# design.net
KiCad netlist of a schematic drawn in EasyEDA Pro
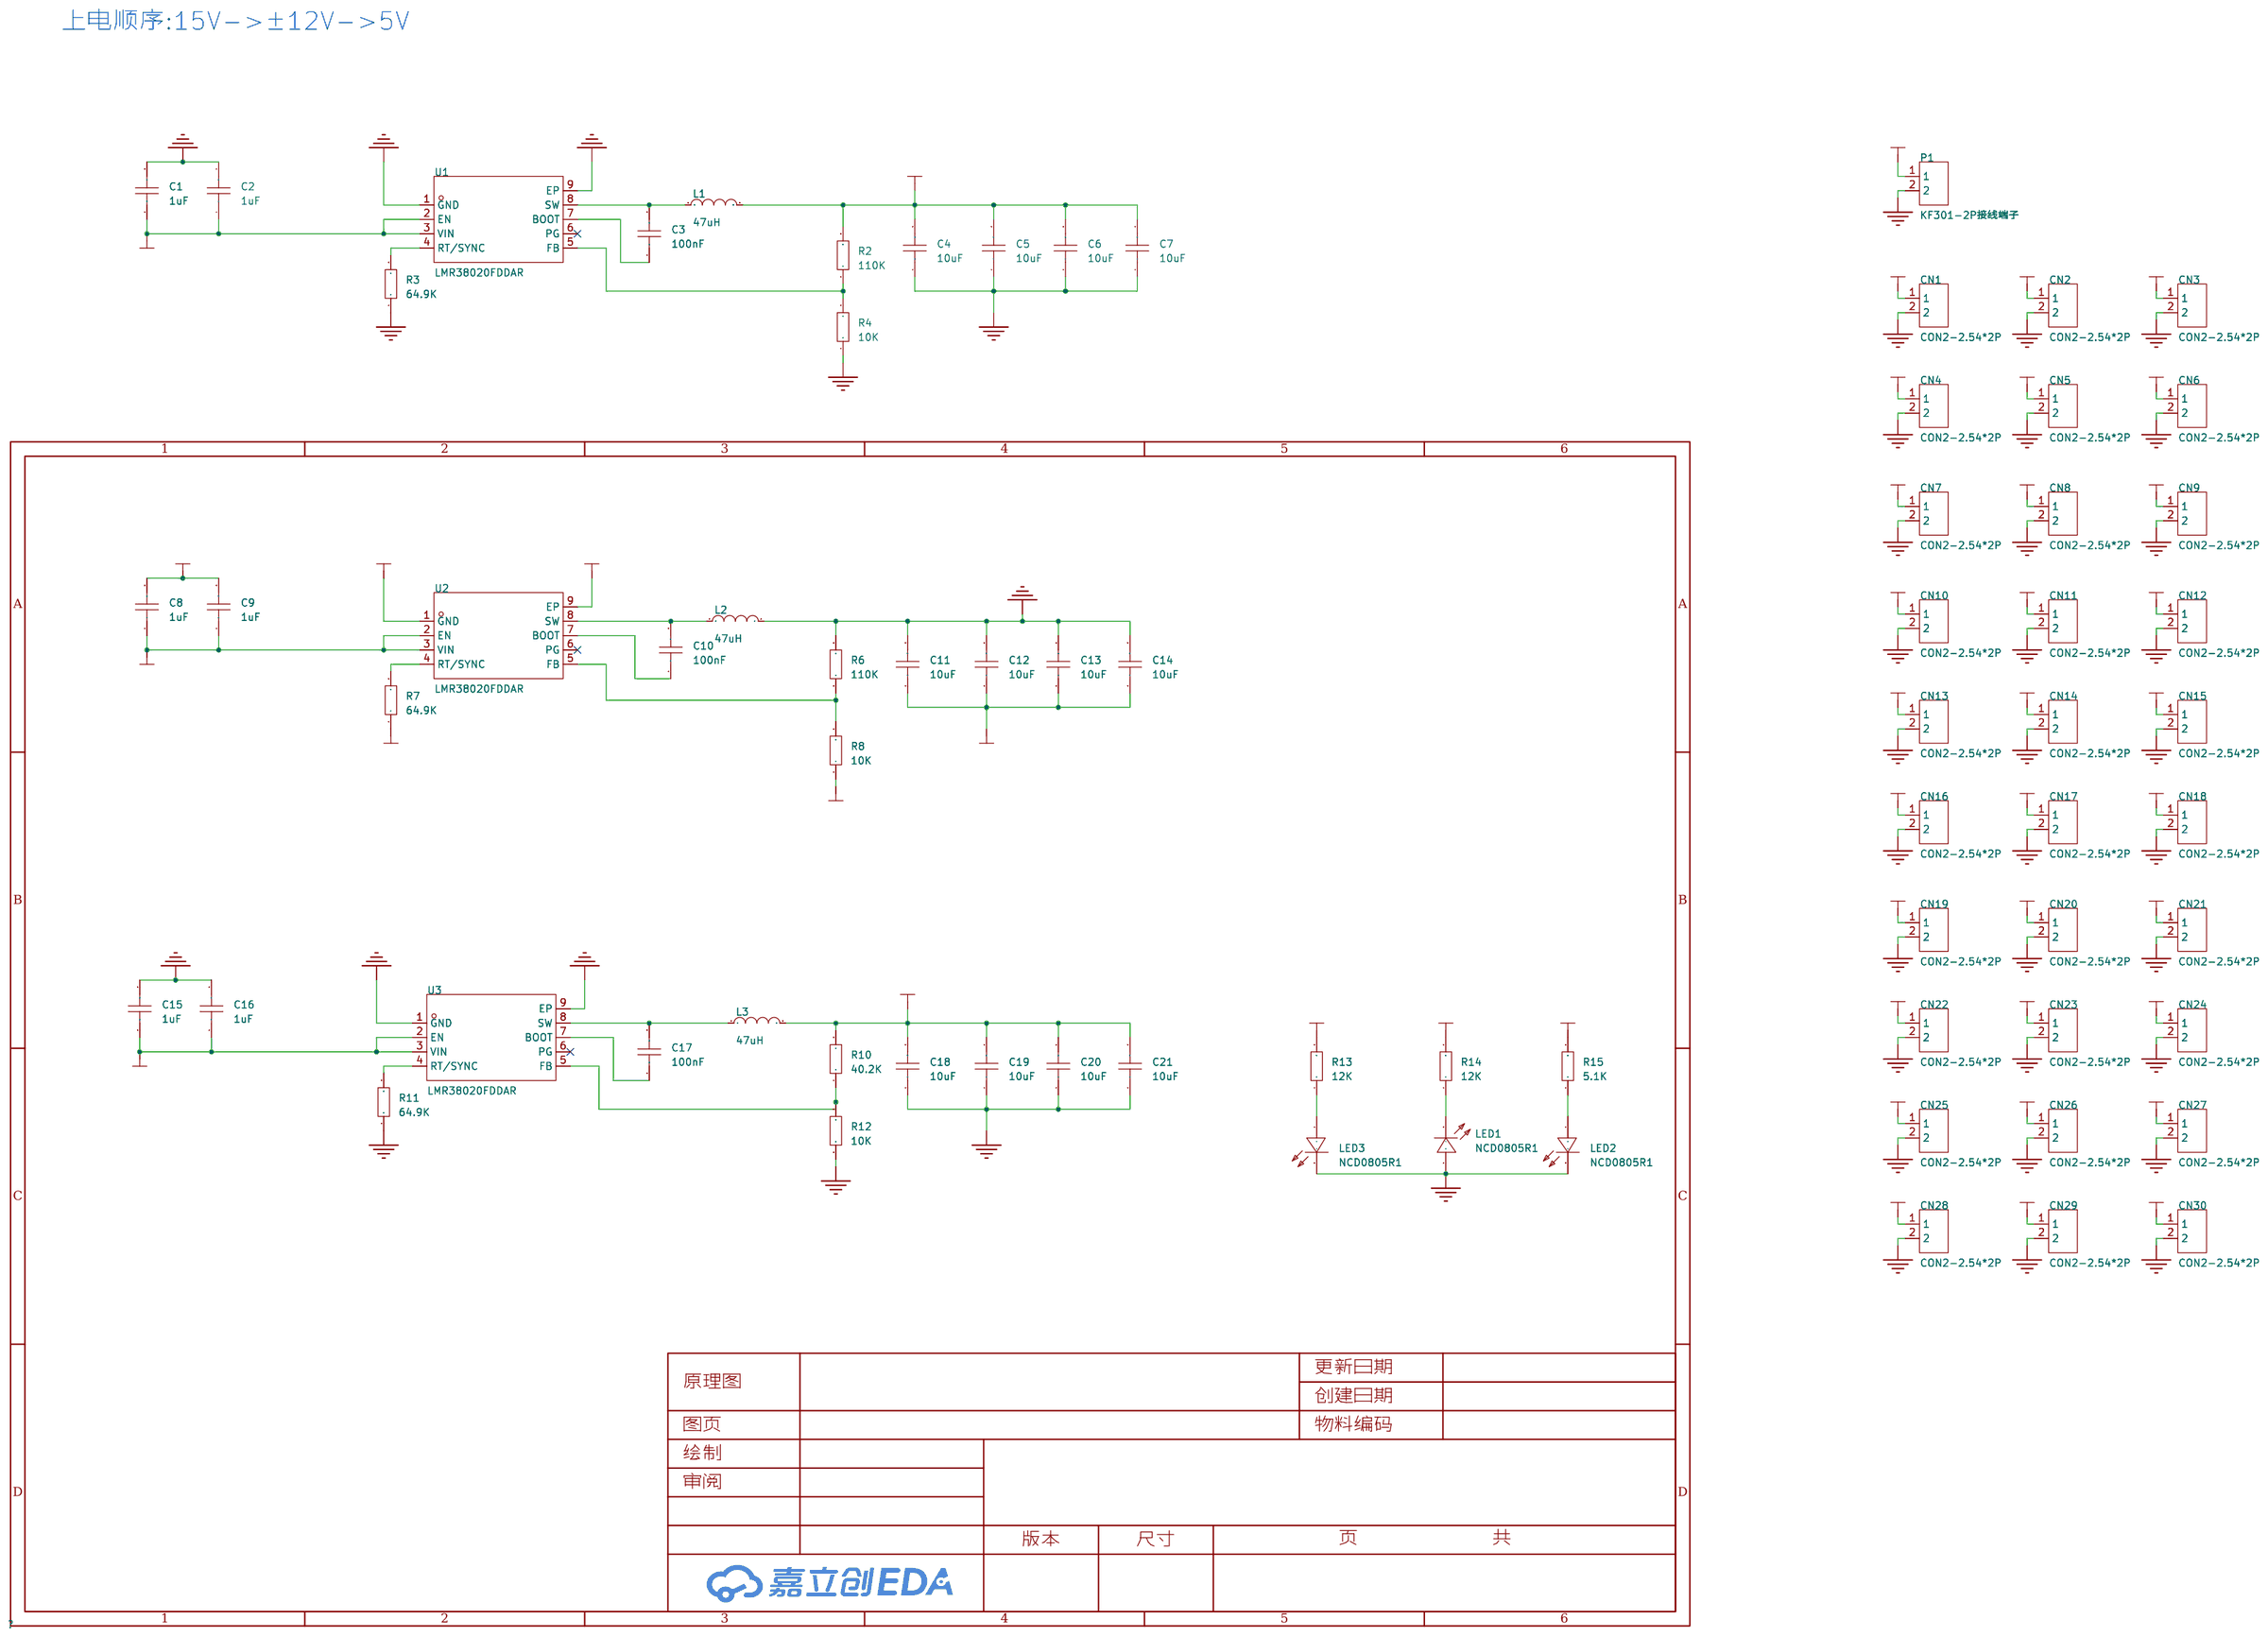
[diagram p0: schematic sheet]

(export (version "E")
  (design (tool "Eeschema 10.0.6"))
  (components
    (comp (ref "C1")
      (value "1uF")
      (footprint "easyedapro:C1206")
      (description "容值:1uF;精度:±10%;额定电压:100V;温度系数:X7R;")
      (fields (field (name "Manufacturer Part") "1206B105K101NT") (field (name "Manufacturer") "FH(风华)"))
      (libsource (lib "easyedapro") (part "1206B105K101NT"))
    )
    (comp (ref "C2")
      (value "1uF")
      (footprint "easyedapro:C1206")
      (description "容值:1uF;精度:±10%;额定电压:100V;温度系数:X7R;")
      (fields (field (name "Manufacturer Part") "1206B105K101NT") (field (name "Manufacturer") "FH(风华)"))
      (libsource (lib "easyedapro") (part "1206B105K101NT"))
    )
    (comp (ref "C3")
      (value "100nF")
      (footprint "easyedapro:C0805")
      (libsource (lib "easyedapro") (part "Capacitance"))
    )
    (comp (ref "C4")
      (value "10uF")
      (footprint "easyedapro:C1206")
      (description "容值:10uF;精度:±10%;额定电压:50V;材质(温度系数):X7R;")
      (fields
        (field (name "Manufacturer Part") "CL31B106KBHNNNE")
        (field (name "Manufacturer") "SAMSUNG(三星)")
      )
      (libsource (lib "easyedapro") (part "CL31B106KBHNNNE"))
    )
    (comp (ref "C5")
      (value "10uF")
      (footprint "easyedapro:C1206")
      (description "容值:10uF;精度:±10%;额定电压:50V;材质(温度系数):X7R;")
      (fields
        (field (name "Manufacturer Part") "CL31B106KBHNNNE")
        (field (name "Manufacturer") "SAMSUNG(三星)")
      )
      (libsource (lib "easyedapro") (part "CL31B106KBHNNNE"))
    )
    (comp (ref "C6")
      (value "10uF")
      (footprint "easyedapro:C1206")
      (description "容值:10uF;精度:±10%;额定电压:50V;材质(温度系数):X7R;")
      (fields
        (field (name "Manufacturer Part") "CL31B106KBHNNNE")
        (field (name "Manufacturer") "SAMSUNG(三星)")
      )
      (libsource (lib "easyedapro") (part "CL31B106KBHNNNE"))
    )
    (comp (ref "C7")
      (value "10uF")
      (footprint "easyedapro:C1206")
      (description "容值:10uF;精度:±10%;额定电压:50V;材质(温度系数):X7R;")
      (fields
        (field (name "Manufacturer Part") "CL31B106KBHNNNE")
        (field (name "Manufacturer") "SAMSUNG(三星)")
      )
      (libsource (lib "easyedapro") (part "CL31B106KBHNNNE"))
    )
    (comp (ref "C8")
      (value "1uF")
      (footprint "easyedapro:C1206")
      (description "容值:1uF;精度:±10%;额定电压:100V;温度系数:X7R;")
      (fields (field (name "Manufacturer Part") "1206B105K101NT") (field (name "Manufacturer") "FH(风华)"))
      (libsource (lib "easyedapro") (part "1206B105K101NT"))
    )
    (comp (ref "C9")
      (value "1uF")
      (footprint "easyedapro:C1206")
      (description "容值:1uF;精度:±10%;额定电压:100V;温度系数:X7R;")
      (fields (field (name "Manufacturer Part") "1206B105K101NT") (field (name "Manufacturer") "FH(风华)"))
      (libsource (lib "easyedapro") (part "1206B105K101NT"))
    )
    (comp (ref "C10")
      (value "100nF")
      (footprint "easyedapro:C0805")
      (libsource (lib "easyedapro") (part "Capacitance"))
    )
    (comp (ref "C11")
      (value "10uF")
      (footprint "easyedapro:C1206")
      (description "容值:10uF;精度:±10%;额定电压:50V;材质(温度系数):X7R;")
      (fields
        (field (name "Manufacturer Part") "CL31B106KBHNNNE")
        (field (name "Manufacturer") "SAMSUNG(三星)")
      )
      (libsource (lib "easyedapro") (part "CL31B106KBHNNNE"))
    )
    (comp (ref "C12")
      (value "10uF")
      (footprint "easyedapro:C1206")
      (description "容值:10uF;精度:±10%;额定电压:50V;材质(温度系数):X7R;")
      (fields
        (field (name "Manufacturer Part") "CL31B106KBHNNNE")
        (field (name "Manufacturer") "SAMSUNG(三星)")
      )
      (libsource (lib "easyedapro") (part "CL31B106KBHNNNE"))
    )
    (comp (ref "C13")
      (value "10uF")
      (footprint "easyedapro:C1206")
      (description "容值:10uF;精度:±10%;额定电压:50V;材质(温度系数):X7R;")
      (fields
        (field (name "Manufacturer Part") "CL31B106KBHNNNE")
        (field (name "Manufacturer") "SAMSUNG(三星)")
      )
      (libsource (lib "easyedapro") (part "CL31B106KBHNNNE"))
    )
    (comp (ref "C14")
      (value "10uF")
      (footprint "easyedapro:C1206")
      (description "容值:10uF;精度:±10%;额定电压:50V;材质(温度系数):X7R;")
      (fields
        (field (name "Manufacturer Part") "CL31B106KBHNNNE")
        (field (name "Manufacturer") "SAMSUNG(三星)")
      )
      (libsource (lib "easyedapro") (part "CL31B106KBHNNNE"))
    )
    (comp (ref "C15")
      (value "1uF")
      (footprint "easyedapro:C1206")
      (description "容值:1uF;精度:±10%;额定电压:100V;温度系数:X7R;")
      (fields (field (name "Manufacturer Part") "1206B105K101NT") (field (name "Manufacturer") "FH(风华)"))
      (libsource (lib "easyedapro") (part "1206B105K101NT"))
    )
    (comp (ref "C16")
      (value "1uF")
      (footprint "easyedapro:C1206")
      (description "容值:1uF;精度:±10%;额定电压:100V;温度系数:X7R;")
      (fields (field (name "Manufacturer Part") "1206B105K101NT") (field (name "Manufacturer") "FH(风华)"))
      (libsource (lib "easyedapro") (part "1206B105K101NT"))
    )
    (comp (ref "C17")
      (value "100nF")
      (footprint "easyedapro:C0805")
      (libsource (lib "easyedapro") (part "Capacitance"))
    )
    (comp (ref "C18")
      (value "10uF")
      (footprint "easyedapro:C1206")
      (description "容值:10uF;精度:±10%;额定电压:50V;材质(温度系数):X7R;")
      (fields
        (field (name "Manufacturer Part") "CL31B106KBHNNNE")
        (field (name "Manufacturer") "SAMSUNG(三星)")
      )
      (libsource (lib "easyedapro") (part "CL31B106KBHNNNE"))
    )
    (comp (ref "C19")
      (value "10uF")
      (footprint "easyedapro:C1206")
      (description "容值:10uF;精度:±10%;额定电压:50V;材质(温度系数):X7R;")
      (fields
        (field (name "Manufacturer Part") "CL31B106KBHNNNE")
        (field (name "Manufacturer") "SAMSUNG(三星)")
      )
      (libsource (lib "easyedapro") (part "CL31B106KBHNNNE"))
    )
    (comp (ref "C20")
      (value "10uF")
      (footprint "easyedapro:C1206")
      (description "容值:10uF;精度:±10%;额定电压:50V;材质(温度系数):X7R;")
      (fields
        (field (name "Manufacturer Part") "CL31B106KBHNNNE")
        (field (name "Manufacturer") "SAMSUNG(三星)")
      )
      (libsource (lib "easyedapro") (part "CL31B106KBHNNNE"))
    )
    (comp (ref "C21")
      (value "10uF")
      (footprint "easyedapro:C1206")
      (description "容值:10uF;精度:±10%;额定电压:50V;材质(温度系数):X7R;")
      (fields
        (field (name "Manufacturer Part") "CL31B106KBHNNNE")
        (field (name "Manufacturer") "SAMSUNG(三星)")
      )
      (libsource (lib "easyedapro") (part "CL31B106KBHNNNE"))
    )
    (comp (ref "CN1")
      (value "CON2-2.54*2P")
      (footprint "easyedapro:CONN-TH_2P-P2.54-V")
      (libsource (lib "easyedapro") (part "CON2-2.54*2P"))
    )
    (comp (ref "CN2")
      (value "CON2-2.54*2P")
      (footprint "easyedapro:CONN-TH_2P-P2.54-V")
      (libsource (lib "easyedapro") (part "CON2-2.54*2P"))
    )
    (comp (ref "CN3")
      (value "CON2-2.54*2P")
      (footprint "easyedapro:CONN-TH_2P-P2.54-V")
      (libsource (lib "easyedapro") (part "CON2-2.54*2P"))
    )
    (comp (ref "CN4")
      (value "CON2-2.54*2P")
      (footprint "easyedapro:CONN-TH_2P-P2.54-V")
      (libsource (lib "easyedapro") (part "CON2-2.54*2P"))
    )
    (comp (ref "CN5")
      (value "CON2-2.54*2P")
      (footprint "easyedapro:CONN-TH_2P-P2.54-V")
      (libsource (lib "easyedapro") (part "CON2-2.54*2P"))
    )
    (comp (ref "CN6")
      (value "CON2-2.54*2P")
      (footprint "easyedapro:CONN-TH_2P-P2.54-V")
      (libsource (lib "easyedapro") (part "CON2-2.54*2P"))
    )
    (comp (ref "CN7")
      (value "CON2-2.54*2P")
      (footprint "easyedapro:CONN-TH_2P-P2.54-V")
      (libsource (lib "easyedapro") (part "CON2-2.54*2P"))
    )
    (comp (ref "CN8")
      (value "CON2-2.54*2P")
      (footprint "easyedapro:CONN-TH_2P-P2.54-V")
      (libsource (lib "easyedapro") (part "CON2-2.54*2P"))
    )
    (comp (ref "CN9")
      (value "CON2-2.54*2P")
      (footprint "easyedapro:CONN-TH_2P-P2.54-V")
      (libsource (lib "easyedapro") (part "CON2-2.54*2P"))
    )
    (comp (ref "CN10")
      (value "CON2-2.54*2P")
      (footprint "easyedapro:CONN-TH_2P-P2.54-V")
      (libsource (lib "easyedapro") (part "CON2-2.54*2P"))
    )
    (comp (ref "CN11")
      (value "CON2-2.54*2P")
      (footprint "easyedapro:CONN-TH_2P-P2.54-V")
      (libsource (lib "easyedapro") (part "CON2-2.54*2P"))
    )
    (comp (ref "CN12")
      (value "CON2-2.54*2P")
      (footprint "easyedapro:CONN-TH_2P-P2.54-V")
      (libsource (lib "easyedapro") (part "CON2-2.54*2P"))
    )
    (comp (ref "CN13")
      (value "CON2-2.54*2P")
      (footprint "easyedapro:CONN-TH_2P-P2.54-V")
      (libsource (lib "easyedapro") (part "CON2-2.54*2P"))
    )
    (comp (ref "CN14")
      (value "CON2-2.54*2P")
      (footprint "easyedapro:CONN-TH_2P-P2.54-V")
      (libsource (lib "easyedapro") (part "CON2-2.54*2P"))
    )
    (comp (ref "CN15")
      (value "CON2-2.54*2P")
      (footprint "easyedapro:CONN-TH_2P-P2.54-V")
      (libsource (lib "easyedapro") (part "CON2-2.54*2P"))
    )
    (comp (ref "CN16")
      (value "CON2-2.54*2P")
      (footprint "easyedapro:CONN-TH_2P-P2.54-V")
      (libsource (lib "easyedapro") (part "CON2-2.54*2P"))
    )
    (comp (ref "CN17")
      (value "CON2-2.54*2P")
      (footprint "easyedapro:CONN-TH_2P-P2.54-V")
      (libsource (lib "easyedapro") (part "CON2-2.54*2P"))
    )
    (comp (ref "CN18")
      (value "CON2-2.54*2P")
      (footprint "easyedapro:CONN-TH_2P-P2.54-V")
      (libsource (lib "easyedapro") (part "CON2-2.54*2P"))
    )
    (comp (ref "CN19")
      (value "CON2-2.54*2P")
      (footprint "easyedapro:CONN-TH_2P-P2.54-V")
      (libsource (lib "easyedapro") (part "CON2-2.54*2P"))
    )
    (comp (ref "CN20")
      (value "CON2-2.54*2P")
      (footprint "easyedapro:CONN-TH_2P-P2.54-V")
      (libsource (lib "easyedapro") (part "CON2-2.54*2P"))
    )
    (comp (ref "CN21")
      (value "CON2-2.54*2P")
      (footprint "easyedapro:CONN-TH_2P-P2.54-V")
      (libsource (lib "easyedapro") (part "CON2-2.54*2P"))
    )
    (comp (ref "CN22")
      (value "CON2-2.54*2P")
      (footprint "easyedapro:CONN-TH_2P-P2.54-V")
      (libsource (lib "easyedapro") (part "CON2-2.54*2P"))
    )
    (comp (ref "CN23")
      (value "CON2-2.54*2P")
      (footprint "easyedapro:CONN-TH_2P-P2.54-V")
      (libsource (lib "easyedapro") (part "CON2-2.54*2P"))
    )
    (comp (ref "CN24")
      (value "CON2-2.54*2P")
      (footprint "easyedapro:CONN-TH_2P-P2.54-V")
      (libsource (lib "easyedapro") (part "CON2-2.54*2P"))
    )
    (comp (ref "CN25")
      (value "CON2-2.54*2P")
      (footprint "easyedapro:CONN-TH_2P-P2.54-V")
      (libsource (lib "easyedapro") (part "CON2-2.54*2P"))
    )
    (comp (ref "CN26")
      (value "CON2-2.54*2P")
      (footprint "easyedapro:CONN-TH_2P-P2.54-V")
      (libsource (lib "easyedapro") (part "CON2-2.54*2P"))
    )
    (comp (ref "CN27")
      (value "CON2-2.54*2P")
      (footprint "easyedapro:CONN-TH_2P-P2.54-V")
      (libsource (lib "easyedapro") (part "CON2-2.54*2P"))
    )
    (comp (ref "CN28")
      (value "CON2-2.54*2P")
      (footprint "easyedapro:CONN-TH_2P-P2.54-V")
      (libsource (lib "easyedapro") (part "CON2-2.54*2P"))
    )
    (comp (ref "CN29")
      (value "CON2-2.54*2P")
      (footprint "easyedapro:CONN-TH_2P-P2.54-V")
      (libsource (lib "easyedapro") (part "CON2-2.54*2P"))
    )
    (comp (ref "CN30")
      (value "CON2-2.54*2P")
      (footprint "easyedapro:CONN-TH_2P-P2.54-V")
      (libsource (lib "easyedapro") (part "CON2-2.54*2P"))
    )
    (comp (ref "L1")
      (value "47uH")
      (footprint "easyedapro:IND-SMD_L11.5-W10.0_FXL1040")
      (description "电感值:47uH;精度:±20%;额定电流:3.3A;饱和电流(Isat):3.5A;类型:一体成型电感;")
      (fields (field (name "Manufacturer Part") "FXL1040-470-M") (field (name "Manufacturer") "cjiang(长江微电)"))
      (libsource (lib "easyedapro") (part "FXL1040-470-M"))
    )
    (comp (ref "L2")
      (value "47uH")
      (footprint "easyedapro:IND-SMD_L11.5-W10.0_FXL1040")
      (description "电感值:47uH;精度:±20%;额定电流:3.3A;饱和电流(Isat):3.5A;类型:一体成型电感;")
      (fields (field (name "Manufacturer Part") "FXL1040-470-M") (field (name "Manufacturer") "cjiang(长江微电)"))
      (libsource (lib "easyedapro") (part "FXL1040-470-M"))
    )
    (comp (ref "L3")
      (value "47uH")
      (footprint "easyedapro:IND-SMD_L11.5-W10.0_FXL1040")
      (description "电感值:47uH;精度:±20%;额定电流:3.3A;饱和电流(Isat):3.5A;类型:一体成型电感;")
      (fields (field (name "Manufacturer Part") "FXL1040-470-M") (field (name "Manufacturer") "cjiang(长江微电)"))
      (libsource (lib "easyedapro") (part "FXL1040-470-M"))
    )
    (comp (ref "LED1")
      (value "NCD0805R1")
      (footprint "easyedapro:LED0805-R-RD")
      (fields (field (name "Manufacturer") "国星光电"))
      (libsource (lib "easyedapro") (part "FC-2012HRK-620D"))
    )
    (comp (ref "LED2")
      (value "NCD0805R1")
      (footprint "easyedapro:LED0805-R-RD")
      (fields (field (name "Manufacturer") "国星光电"))
      (libsource (lib "easyedapro") (part "FC-2012HRK-620D"))
    )
    (comp (ref "LED3")
      (value "NCD0805R1")
      (footprint "easyedapro:LED0805-R-RD")
      (fields (field (name "Manufacturer") "国星光电"))
      (libsource (lib "easyedapro") (part "FC-2012HRK-620D"))
    )
    (comp (ref "P1")
      (value "KF301-2P接线端子")
      (footprint "easyedapro:CONN-TH_XY301V-A-5.0-2P")
      (libsource (lib "easyedapro") (part "KF301-2P接线端子"))
    )
    (comp (ref "R2") (value "110K") (footprint "easyedapro:R0805") (libsource (lib "easyedapro") (part "电阻")))
    (comp (ref "R3")
      (value "64.9K")
      (footprint "easyedapro:R0805")
      (libsource (lib "easyedapro") (part "电阻"))
    )
    (comp (ref "R4") (value "10K") (footprint "easyedapro:R0805") (libsource (lib "easyedapro") (part "电阻")))
    (comp (ref "R6") (value "110K") (footprint "easyedapro:R0805") (libsource (lib "easyedapro") (part "电阻")))
    (comp (ref "R7")
      (value "64.9K")
      (footprint "easyedapro:R0805")
      (libsource (lib "easyedapro") (part "电阻"))
    )
    (comp (ref "R8") (value "10K") (footprint "easyedapro:R0805") (libsource (lib "easyedapro") (part "电阻")))
    (comp (ref "R10")
      (value "40.2K")
      (footprint "easyedapro:R0805")
      (libsource (lib "easyedapro") (part "电阻"))
    )
    (comp (ref "R11")
      (value "64.9K")
      (footprint "easyedapro:R0805")
      (libsource (lib "easyedapro") (part "电阻"))
    )
    (comp (ref "R12") (value "10K") (footprint "easyedapro:R0805") (libsource (lib "easyedapro") (part "电阻")))
    (comp (ref "R13") (value "12K") (footprint "easyedapro:R0805") (libsource (lib "easyedapro") (part "电阻")))
    (comp (ref "R14") (value "12K") (footprint "easyedapro:R0805") (libsource (lib "easyedapro") (part "电阻")))
    (comp (ref "R15")
      (value "5.1K")
      (footprint "easyedapro:R0805")
      (libsource (lib "easyedapro") (part "电阻"))
    )
    (comp (ref "U1")
      (value "LMR38020FDDAR")
      (footprint "easyedapro:ESOP-8_L4.9-W3.9-P1.27-LS6.0-BL-EP-1")
      (description "功能类型:降压型;输出类型:-;工作电压:4.2V~80V;输出电压:-;输出电流:2A;")
      (fields (field (name "Manufacturer") "TI(德州仪器)"))
      (libsource (lib "easyedapro") (part "LMR38020FDDAR"))
    )
    (comp (ref "U2")
      (value "LMR38020FDDAR")
      (footprint "easyedapro:ESOP-8_L4.9-W3.9-P1.27-LS6.0-BL-EP-1")
      (description "功能类型:降压型;输出类型:-;工作电压:4.2V~80V;输出电压:-;输出电流:2A;")
      (fields (field (name "Manufacturer") "TI(德州仪器)"))
      (libsource (lib "easyedapro") (part "LMR38020FDDAR"))
    )
    (comp (ref "U3")
      (value "LMR38020FDDAR")
      (footprint "easyedapro:ESOP-8_L4.9-W3.9-P1.27-LS6.0-BL-EP-1")
      (description "功能类型:降压型;输出类型:-;工作电压:4.2V~80V;输出电压:-;输出电流:2A;")
      (fields (field (name "Manufacturer") "TI(德州仪器)"))
      (libsource (lib "easyedapro") (part "LMR38020FDDAR"))
    )
  )
  (nets
    (net (code "1") (name "+5V") (class "Default")
      (node (ref "C18") (pin "2") (pinfunction "2_2") (pintype "unspecified"))
      (node (ref "C19") (pin "2") (pinfunction "2_2") (pintype "unspecified"))
      (node (ref "C20") (pin "2") (pinfunction "2_2") (pintype "unspecified"))
      (node (ref "C21") (pin "2") (pinfunction "2_2") (pintype "unspecified"))
      (node (ref "CN11") (pin "1") (pinfunction "1_1") (pintype "unspecified"))
      (node (ref "CN14") (pin "1") (pinfunction "1_1") (pintype "unspecified"))
      (node (ref "CN17") (pin "1") (pinfunction "1_1") (pintype "unspecified"))
      (node (ref "CN2") (pin "1") (pinfunction "1_1") (pintype "unspecified"))
      (node (ref "CN20") (pin "1") (pinfunction "1_1") (pintype "unspecified"))
      (node (ref "CN23") (pin "1") (pinfunction "1_1") (pintype "unspecified"))
      (node (ref "CN26") (pin "1") (pinfunction "1_1") (pintype "unspecified"))
      (node (ref "CN29") (pin "1") (pinfunction "1_1") (pintype "unspecified"))
      (node (ref "CN5") (pin "1") (pinfunction "1_1") (pintype "unspecified"))
      (node (ref "CN8") (pin "1") (pinfunction "1_1") (pintype "unspecified"))
      (node (ref "L3") (pin "2") (pinfunction "2_2") (pintype "unspecified"))
      (node (ref "R10") (pin "2") (pinfunction "2_2") (pintype "input"))
      (node (ref "R15") (pin "2") (pinfunction "2_2") (pintype "input"))
    )
    (net (code "2") (name "+12V") (class "Default")
      (node (ref "C4") (pin "2") (pinfunction "2_2") (pintype "unspecified"))
      (node (ref "C5") (pin "2") (pinfunction "2_2") (pintype "unspecified"))
      (node (ref "C6") (pin "2") (pinfunction "2_2") (pintype "unspecified"))
      (node (ref "C7") (pin "2") (pinfunction "2_2") (pintype "unspecified"))
      (node (ref "C8") (pin "1") (pinfunction "1_1") (pintype "unspecified"))
      (node (ref "C9") (pin "1") (pinfunction "1_1") (pintype "unspecified"))
      (node (ref "CN1") (pin "1") (pinfunction "1_1") (pintype "unspecified"))
      (node (ref "CN10") (pin "1") (pinfunction "1_1") (pintype "unspecified"))
      (node (ref "CN13") (pin "1") (pinfunction "1_1") (pintype "unspecified"))
      (node (ref "CN16") (pin "1") (pinfunction "1_1") (pintype "unspecified"))
      (node (ref "CN19") (pin "1") (pinfunction "1_1") (pintype "unspecified"))
      (node (ref "CN22") (pin "1") (pinfunction "1_1") (pintype "unspecified"))
      (node (ref "CN25") (pin "1") (pinfunction "1_1") (pintype "unspecified"))
      (node (ref "CN28") (pin "1") (pinfunction "1_1") (pintype "unspecified"))
      (node (ref "CN4") (pin "1") (pinfunction "1_1") (pintype "unspecified"))
      (node (ref "CN7") (pin "1") (pinfunction "1_1") (pintype "unspecified"))
      (node (ref "L1") (pin "2") (pinfunction "2_2") (pintype "unspecified"))
      (node (ref "R13") (pin "2") (pinfunction "2_2") (pintype "input"))
      (node (ref "R2") (pin "2") (pinfunction "2_2") (pintype "input"))
      (node (ref "U2") (pin "2") (pinfunction "EN_2") (pintype "unspecified"))
      (node (ref "U2") (pin "3") (pinfunction "VIN_3") (pintype "unspecified"))
    )
    (net (code "3") (name "-12V") (class "Default")
      (node (ref "C11") (pin "1") (pinfunction "1_1") (pintype "unspecified"))
      (node (ref "C12") (pin "1") (pinfunction "1_1") (pintype "unspecified"))
      (node (ref "C13") (pin "1") (pinfunction "1_1") (pintype "unspecified"))
      (node (ref "C14") (pin "1") (pinfunction "1_1") (pintype "unspecified"))
      (node (ref "C8") (pin "2") (pinfunction "2_2") (pintype "unspecified"))
      (node (ref "C9") (pin "2") (pinfunction "2_2") (pintype "unspecified"))
      (node (ref "CN12") (pin "1") (pinfunction "1_1") (pintype "unspecified"))
      (node (ref "CN15") (pin "1") (pinfunction "1_1") (pintype "unspecified"))
      (node (ref "CN18") (pin "1") (pinfunction "1_1") (pintype "unspecified"))
      (node (ref "CN21") (pin "1") (pinfunction "1_1") (pintype "unspecified"))
      (node (ref "CN24") (pin "1") (pinfunction "1_1") (pintype "unspecified"))
      (node (ref "CN27") (pin "1") (pinfunction "1_1") (pintype "unspecified"))
      (node (ref "CN3") (pin "1") (pinfunction "1_1") (pintype "unspecified"))
      (node (ref "CN30") (pin "1") (pinfunction "1_1") (pintype "unspecified"))
      (node (ref "CN6") (pin "1") (pinfunction "1_1") (pintype "unspecified"))
      (node (ref "CN9") (pin "1") (pinfunction "1_1") (pintype "unspecified"))
      (node (ref "R14") (pin "2") (pinfunction "2_2") (pintype "input"))
      (node (ref "R7") (pin "1") (pinfunction "1_1") (pintype "input"))
      (node (ref "R8") (pin "1") (pinfunction "1_1") (pintype "input"))
      (node (ref "U2") (pin "1") (pinfunction "GND_1") (pintype "unspecified"))
      (node (ref "U2") (pin "9") (pinfunction "EP_9") (pintype "unspecified"))
    )
    (net (code "4") (name "GND") (class "Default")
      (node (ref "C1") (pin "2") (pinfunction "2_2") (pintype "unspecified"))
      (node (ref "C11") (pin "2") (pinfunction "2_2") (pintype "unspecified"))
      (node (ref "C12") (pin "2") (pinfunction "2_2") (pintype "unspecified"))
      (node (ref "C13") (pin "2") (pinfunction "2_2") (pintype "unspecified"))
      (node (ref "C14") (pin "2") (pinfunction "2_2") (pintype "unspecified"))
      (node (ref "C15") (pin "2") (pinfunction "2_2") (pintype "unspecified"))
      (node (ref "C16") (pin "2") (pinfunction "2_2") (pintype "unspecified"))
      (node (ref "C18") (pin "1") (pinfunction "1_1") (pintype "unspecified"))
      (node (ref "C19") (pin "1") (pinfunction "1_1") (pintype "unspecified"))
      (node (ref "C2") (pin "2") (pinfunction "2_2") (pintype "unspecified"))
      (node (ref "C20") (pin "1") (pinfunction "1_1") (pintype "unspecified"))
      (node (ref "C21") (pin "1") (pinfunction "1_1") (pintype "unspecified"))
      (node (ref "C4") (pin "1") (pinfunction "1_1") (pintype "unspecified"))
      (node (ref "C5") (pin "1") (pinfunction "1_1") (pintype "unspecified"))
      (node (ref "C6") (pin "1") (pinfunction "1_1") (pintype "unspecified"))
      (node (ref "C7") (pin "1") (pinfunction "1_1") (pintype "unspecified"))
      (node (ref "CN1") (pin "2") (pinfunction "2_2") (pintype "unspecified"))
      (node (ref "CN10") (pin "2") (pinfunction "2_2") (pintype "unspecified"))
      (node (ref "CN11") (pin "2") (pinfunction "2_2") (pintype "unspecified"))
      (node (ref "CN12") (pin "2") (pinfunction "2_2") (pintype "unspecified"))
      (node (ref "CN13") (pin "2") (pinfunction "2_2") (pintype "unspecified"))
      (node (ref "CN14") (pin "2") (pinfunction "2_2") (pintype "unspecified"))
      (node (ref "CN15") (pin "2") (pinfunction "2_2") (pintype "unspecified"))
      (node (ref "CN16") (pin "2") (pinfunction "2_2") (pintype "unspecified"))
      (node (ref "CN17") (pin "2") (pinfunction "2_2") (pintype "unspecified"))
      (node (ref "CN18") (pin "2") (pinfunction "2_2") (pintype "unspecified"))
      (node (ref "CN19") (pin "2") (pinfunction "2_2") (pintype "unspecified"))
      (node (ref "CN2") (pin "2") (pinfunction "2_2") (pintype "unspecified"))
      (node (ref "CN20") (pin "2") (pinfunction "2_2") (pintype "unspecified"))
      (node (ref "CN21") (pin "2") (pinfunction "2_2") (pintype "unspecified"))
      (node (ref "CN22") (pin "2") (pinfunction "2_2") (pintype "unspecified"))
      (node (ref "CN23") (pin "2") (pinfunction "2_2") (pintype "unspecified"))
      (node (ref "CN24") (pin "2") (pinfunction "2_2") (pintype "unspecified"))
      (node (ref "CN25") (pin "2") (pinfunction "2_2") (pintype "unspecified"))
      (node (ref "CN26") (pin "2") (pinfunction "2_2") (pintype "unspecified"))
      (node (ref "CN27") (pin "2") (pinfunction "2_2") (pintype "unspecified"))
      (node (ref "CN28") (pin "2") (pinfunction "2_2") (pintype "unspecified"))
      (node (ref "CN29") (pin "2") (pinfunction "2_2") (pintype "unspecified"))
      (node (ref "CN3") (pin "2") (pinfunction "2_2") (pintype "unspecified"))
      (node (ref "CN30") (pin "2") (pinfunction "2_2") (pintype "unspecified"))
      (node (ref "CN4") (pin "2") (pinfunction "2_2") (pintype "unspecified"))
      (node (ref "CN5") (pin "2") (pinfunction "2_2") (pintype "unspecified"))
      (node (ref "CN6") (pin "2") (pinfunction "2_2") (pintype "unspecified"))
      (node (ref "CN7") (pin "2") (pinfunction "2_2") (pintype "unspecified"))
      (node (ref "CN8") (pin "2") (pinfunction "2_2") (pintype "unspecified"))
      (node (ref "CN9") (pin "2") (pinfunction "2_2") (pintype "unspecified"))
      (node (ref "L2") (pin "2") (pinfunction "2_2") (pintype "unspecified"))
      (node (ref "LED1") (pin "1") (pinfunction "+_1") (pintype "unspecified"))
      (node (ref "LED2") (pin "2") (pinfunction "-_2") (pintype "unspecified"))
      (node (ref "LED3") (pin "2") (pinfunction "-_2") (pintype "unspecified"))
      (node (ref "P1") (pin "2") (pinfunction "2_2") (pintype "unspecified"))
      (node (ref "R11") (pin "1") (pinfunction "1_1") (pintype "input"))
      (node (ref "R12") (pin "1") (pinfunction "1_1") (pintype "input"))
      (node (ref "R3") (pin "1") (pinfunction "1_1") (pintype "input"))
      (node (ref "R4") (pin "1") (pinfunction "1_1") (pintype "input"))
      (node (ref "R6") (pin "2") (pinfunction "2_2") (pintype "input"))
      (node (ref "U1") (pin "1") (pinfunction "GND_1") (pintype "unspecified"))
      (node (ref "U1") (pin "9") (pinfunction "EP_9") (pintype "unspecified"))
      (node (ref "U3") (pin "1") (pinfunction "GND_1") (pintype "unspecified"))
      (node (ref "U3") (pin "9") (pinfunction "EP_9") (pintype "unspecified"))
    )
    (net (code "5") (name "Net-(LED1--)") (class "Default")
      (node (ref "LED1") (pin "2") (pinfunction "-_2") (pintype "unspecified"))
      (node (ref "R14") (pin "1") (pinfunction "1_1") (pintype "input"))
    )
    (net (code "6") (name "Net-(LED2-+)") (class "Default")
      (node (ref "LED2") (pin "1") (pinfunction "+_1") (pintype "unspecified"))
      (node (ref "R15") (pin "1") (pinfunction "1_1") (pintype "input"))
    )
    (net (code "7") (name "Net-(LED3-+)") (class "Default")
      (node (ref "LED3") (pin "1") (pinfunction "+_1") (pintype "unspecified"))
      (node (ref "R13") (pin "1") (pinfunction "1_1") (pintype "input"))
    )
    (net (code "8") (name "Net-(U1-BOOT)") (class "Default")
      (node (ref "C3") (pin "1") (pinfunction "1_1") (pintype "input"))
      (node (ref "U1") (pin "7") (pinfunction "BOOT_7") (pintype "unspecified"))
    )
    (net (code "9") (name "Net-(U1-FB)") (class "Default")
      (node (ref "R2") (pin "1") (pinfunction "1_1") (pintype "input"))
      (node (ref "R4") (pin "2") (pinfunction "2_2") (pintype "input"))
      (node (ref "U1") (pin "5") (pinfunction "FB_5") (pintype "unspecified"))
    )
    (net (code "10") (name "Net-(U1-RT{slash}SYNC)") (class "Default")
      (node (ref "R3") (pin "2") (pinfunction "2_2") (pintype "input"))
      (node (ref "U1") (pin "4") (pinfunction "RT/SYNC_4") (pintype "unspecified"))
    )
    (net (code "11") (name "Net-(U1-SW)") (class "Default")
      (node (ref "C3") (pin "2") (pinfunction "2_2") (pintype "input"))
      (node (ref "L1") (pin "1") (pinfunction "1_1") (pintype "unspecified"))
      (node (ref "U1") (pin "8") (pinfunction "SW_8") (pintype "unspecified"))
    )
    (net (code "12") (name "Net-(U2-BOOT)") (class "Default")
      (node (ref "C10") (pin "1") (pinfunction "1_1") (pintype "input"))
      (node (ref "U2") (pin "7") (pinfunction "BOOT_7") (pintype "unspecified"))
    )
    (net (code "13") (name "Net-(U2-FB)") (class "Default")
      (node (ref "R6") (pin "1") (pinfunction "1_1") (pintype "input"))
      (node (ref "R8") (pin "2") (pinfunction "2_2") (pintype "input"))
      (node (ref "U2") (pin "5") (pinfunction "FB_5") (pintype "unspecified"))
    )
    (net (code "14") (name "Net-(U2-RT{slash}SYNC)") (class "Default")
      (node (ref "R7") (pin "2") (pinfunction "2_2") (pintype "input"))
      (node (ref "U2") (pin "4") (pinfunction "RT/SYNC_4") (pintype "unspecified"))
    )
    (net (code "15") (name "Net-(U2-SW)") (class "Default")
      (node (ref "C10") (pin "2") (pinfunction "2_2") (pintype "input"))
      (node (ref "L2") (pin "1") (pinfunction "1_1") (pintype "unspecified"))
      (node (ref "U2") (pin "8") (pinfunction "SW_8") (pintype "unspecified"))
    )
    (net (code "16") (name "Net-(U3-BOOT)") (class "Default")
      (node (ref "C17") (pin "1") (pinfunction "1_1") (pintype "input"))
      (node (ref "U3") (pin "7") (pinfunction "BOOT_7") (pintype "unspecified"))
    )
    (net (code "17") (name "Net-(U3-FB)") (class "Default")
      (node (ref "R10") (pin "1") (pinfunction "1_1") (pintype "input"))
      (node (ref "R12") (pin "2") (pinfunction "2_2") (pintype "input"))
      (node (ref "U3") (pin "5") (pinfunction "FB_5") (pintype "unspecified"))
    )
    (net (code "18") (name "Net-(U3-RT{slash}SYNC)") (class "Default")
      (node (ref "R11") (pin "2") (pinfunction "2_2") (pintype "input"))
      (node (ref "U3") (pin "4") (pinfunction "RT/SYNC_4") (pintype "unspecified"))
    )
    (net (code "19") (name "Net-(U3-SW)") (class "Default")
      (node (ref "C17") (pin "2") (pinfunction "2_2") (pintype "input"))
      (node (ref "L3") (pin "1") (pinfunction "1_1") (pintype "unspecified"))
      (node (ref "U3") (pin "8") (pinfunction "SW_8") (pintype "unspecified"))
    )
    (net (code "20") (name "VIN") (class "Default")
      (node (ref "C1") (pin "1") (pinfunction "1_1") (pintype "unspecified"))
      (node (ref "C15") (pin "1") (pinfunction "1_1") (pintype "unspecified"))
      (node (ref "C16") (pin "1") (pinfunction "1_1") (pintype "unspecified"))
      (node (ref "C2") (pin "1") (pinfunction "1_1") (pintype "unspecified"))
      (node (ref "P1") (pin "1") (pinfunction "1_1") (pintype "unspecified"))
      (node (ref "U1") (pin "2") (pinfunction "EN_2") (pintype "unspecified"))
      (node (ref "U1") (pin "3") (pinfunction "VIN_3") (pintype "unspecified"))
      (node (ref "U3") (pin "2") (pinfunction "EN_2") (pintype "unspecified"))
      (node (ref "U3") (pin "3") (pinfunction "VIN_3") (pintype "unspecified"))
    )
    (net (code "21") (name "unconnected-(U1-PG-Pad6)") (class "Default")
      (node (ref "U1") (pin "6") (pinfunction "PG_6") (pintype "unspecified+no_connect"))
    )
    (net (code "22") (name "unconnected-(U2-PG-Pad6)") (class "Default")
      (node (ref "U2") (pin "6") (pinfunction "PG_6") (pintype "unspecified+no_connect"))
    )
    (net (code "23") (name "unconnected-(U3-PG-Pad6)") (class "Default")
      (node (ref "U3") (pin "6") (pinfunction "PG_6") (pintype "unspecified+no_connect"))
    )
  )
)
